# Sheet3.net
KiCad netlist of a schematic drawn in Altium Designer
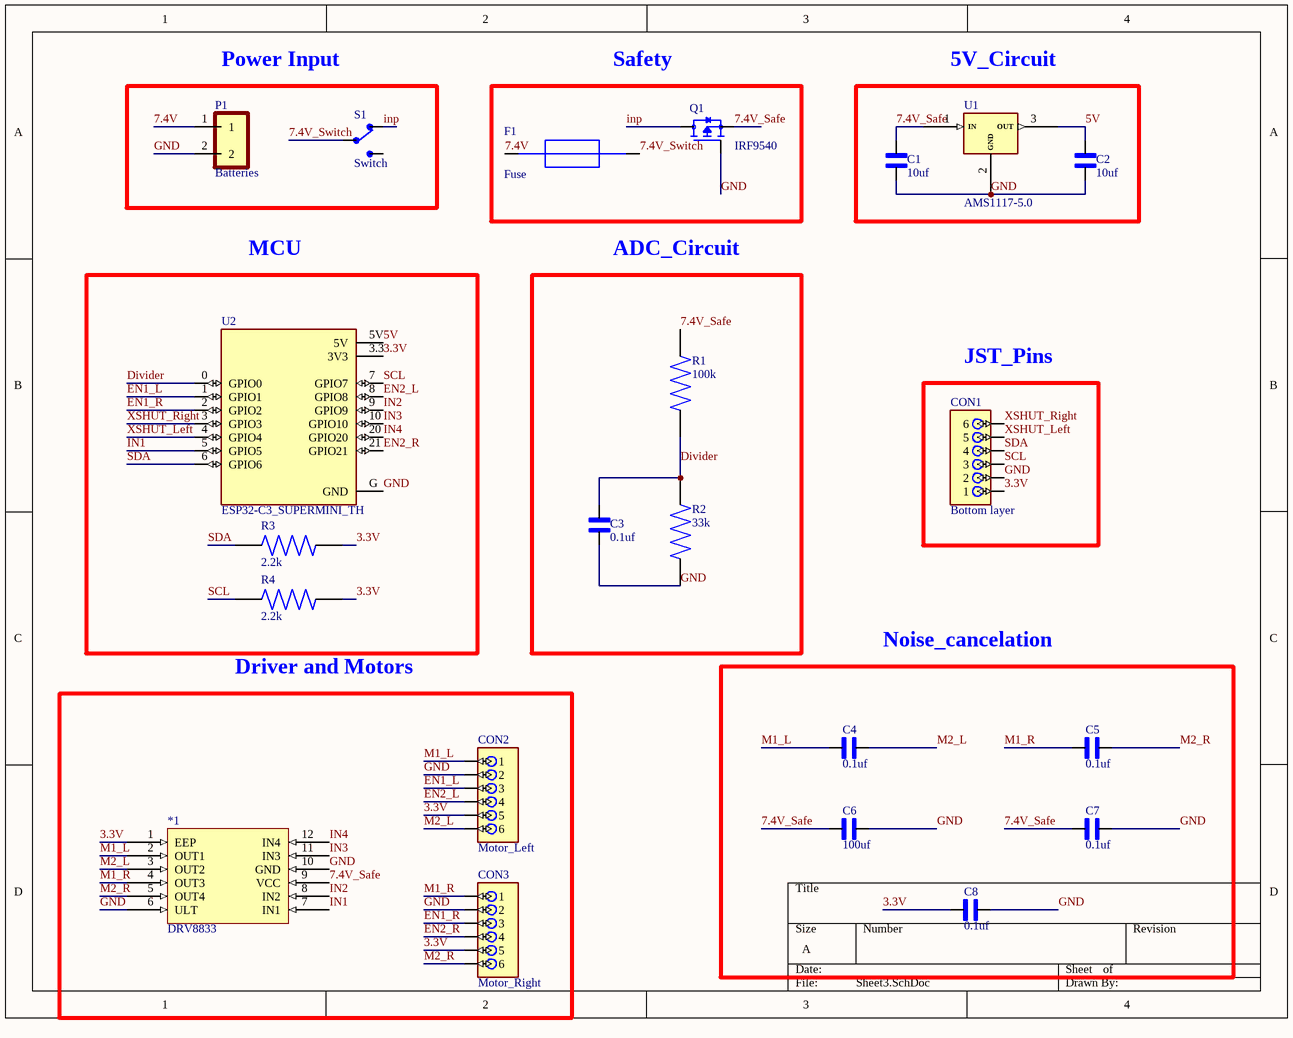
[diagram p0: Sheet3.SchDoc]

(export (version "E")
  (design (tool "Eeschema 10.0.6"))
  (components
    (comp (ref "*1") (value "DRV8833") (footprint "MOD-DRV8833") (libsource (lib "Schlib1") (part "DRV8833")))
    (comp (ref "C1")
      (value "10uf")
      (footprint "CAP_ECHU1H181GX5")
      (description "Capacitor Pps Film, 180pf, 50v, 2%, 0805capacitor Pps Film, 180pf, 50v, 2%, 0805")
      (fields (field (name "MF") "Panasonic") (field (name "DIGI-KEY_PART_NUMBER") "PCF1287TR-ND"))
      (libsource (lib "") (part "ECHU1H181GX5_1"))
    )
    (comp (ref "C2")
      (value "10uf")
      (footprint "CAP_ECHU1H181GX5")
      (description "Capacitor Pps Film, 180pf, 50v, 2%, 0805capacitor Pps Film, 180pf, 50v, 2%, 0805")
      (fields (field (name "MF") "Panasonic") (field (name "DIGI-KEY_PART_NUMBER") "PCF1287TR-ND"))
      (libsource (lib "") (part "ECHU1H181GX5_1"))
    )
    (comp (ref "C3")
      (value "0.1uf")
      (footprint "CAP_ECHU1H181GX5")
      (description "Capacitor Pps Film, 180pf, 50v, 2%, 0805capacitor Pps Film, 180pf, 50v, 2%, 0805")
      (fields (field (name "MF") "Panasonic") (field (name "DIGI-KEY_PART_NUMBER") "PCF1287TR-ND"))
      (libsource (lib "") (part "ECHU1H181GX5_1"))
    )
    (comp (ref "C4")
      (value "0.1uf")
      (footprint "CAP_ECHU1H181GX5")
      (description "Capacitor Pps Film, 180pf, 50v, 2%, 0805capacitor Pps Film, 180pf, 50v, 2%, 0805")
      (fields (field (name "MF") "Panasonic") (field (name "DIGI-KEY_PART_NUMBER") "PCF1287TR-ND"))
      (libsource (lib "Schlib1") (part "ECHU1H181GX5"))
    )
    (comp (ref "C5")
      (value "0.1uf")
      (footprint "CAP_ECHU1H181GX5")
      (description "Capacitor Pps Film, 180pf, 50v, 2%, 0805capacitor Pps Film, 180pf, 50v, 2%, 0805")
      (fields (field (name "MF") "Panasonic") (field (name "DIGI-KEY_PART_NUMBER") "PCF1287TR-ND"))
      (libsource (lib "Schlib1") (part "ECHU1H181GX5"))
    )
    (comp (ref "C6")
      (value "100uf")
      (footprint "CAPC3225X280N")
      (description "100 ÂµF Â±20% 6.3V Ceramic Capacitor X5R 1210 (3225 Metric)")
      (fields (field (name "MF") "Samsung") (field (name "MP") "CL32A107MQVNNWE"))
      (libsource (lib "Schlib1") (part "CL32A107MQVNNWE"))
    )
    (comp (ref "C7")
      (value "0.1uf")
      (footprint "CAPC3225X280N")
      (description "100 ÂµF Â±20% 6.3V Ceramic Capacitor X5R 1210 (3225 Metric)")
      (fields (field (name "MF") "Samsung") (field (name "MP") "CL32A107MQVNNWE"))
      (libsource (lib "Schlib1") (part "CL32A107MQVNNWE"))
    )
    (comp (ref "C8")
      (value "0.1uf")
      (footprint "CAPC3225X280N")
      (description "100 ÂµF Â±20% 6.3V Ceramic Capacitor X5R 1210 (3225 Metric)")
      (fields (field (name "MF") "Samsung") (field (name "MP") "CL32A107MQVNNWE"))
      (libsource (lib "Schlib1") (part "CL32A107MQVNNWE"))
    )
    (comp (ref "CON1")
      (value "Bottom layer")
      (footprint "6 pin JST")
      (description "Connector Header Surface Mount 6 position 0.059 (1.50mm)")
      (fields (field (name "MF") "JST") (field (name "MP") "B6B-ZR"))
      (libsource (lib "") (part "6 pin JST_1"))
    )
    (comp (ref "CON2")
      (value "Motor_Left")
      (footprint "6 pin JST")
      (description "Connector Header Surface Mount 6 position 0.059 (1.50mm)")
      (fields (field (name "MF") "JST") (field (name "MP") "B6B-ZR"))
      (libsource (lib "Schlib1") (part "6 pin JST"))
    )
    (comp (ref "CON3")
      (value "Motor_Right")
      (footprint "6 pin JST")
      (description "Connector Header Surface Mount 6 position 0.059 (1.50mm)")
      (fields (field (name "MF") "JST") (field (name "MP") "B6B-ZR"))
      (libsource (lib "Schlib1") (part "6 pin JST"))
    )
    (comp (ref "F1")
      (value "Fuse")
      (footprint "FUSC3216X75N")
      (description "Polymeric PTC Resettable Fuse 6V 350 mA Ih Surface Mount 1206 (3216 Metric), Concave")
      (fields (field (name "MF") "Littelfuse Inc.") (field (name "MP") "1206L035YR"))
      (libsource (lib "Schlib1") (part "1206L035YR"))
    )
    (comp (ref "P1")
      (value "Batteries")
      (footprint "Green Terminal")
      (fields (field (name "MF") "TE Connectivity") (field (name "MP") "282837-2"))
      (libsource (lib "Schlib1") (part "Green Terminal"))
    )
    (comp (ref "Q1")
      (value "IRF9540")
      (footprint "TO254P1052X465X1989-3")
      (description "P-Channel 100 V 19A (Tc) 3.7W (Ta), 150W (Tc) Surface Mount DÂ²PAK (TO-263)")
      (fields (field (name "MF") "Vishay"))
      (libsource (lib "Schlib1") (part "IRF9540"))
    )
    (comp (ref "R1")
      (value "100k")
      (footprint "SMD R")
      (fields (field (name "MP") "ERJU06F91R0V"))
      (libsource (lib "My_library") (part "SMD R 0805"))
    )
    (comp (ref "R2")
      (value "33k")
      (footprint "SMD R")
      (fields (field (name "MP") "ERJU06F91R0V"))
      (libsource (lib "My_library") (part "SMD R 0805"))
    )
    (comp (ref "R3")
      (value "2.2k")
      (footprint "SMD R")
      (fields (field (name "MP") "ERJU06F91R0V"))
      (libsource (lib "My_library") (part "SMD R 0805"))
    )
    (comp (ref "R4")
      (value "2.2k")
      (footprint "SMD R")
      (fields (field (name "MP") "ERJU06F91R0V"))
      (libsource (lib "My_library") (part "SMD R 0805"))
    )
    (comp (ref "S1")
      (value "Switch")
      (footprint "SW_1101M2S3CQE2")
      (description "Switch,Slide,Sealed,SPDT,ON-NONE-ON,PC Mnt,.200 Blk Act,6A,120VAC,PC Thru-Hole ¦ C&K 1101M2S3CQE2")
      (fields (field (name "MF") "C&K") (field (name "MP") "1101M2S3CQE2"))
      (libsource (lib "My_library") (part "1101M2S3CQE2"))
    )
    (comp (ref "U1")
      (value "AMS1117-5.0")
      (footprint "5V Regulator")
      (libsource (lib "Schlib1") (part "5V Regulator"))
    )
    (comp (ref "U2")
      (value "ESP32-C3_SUPERMINI_TH")
      (footprint "MODULE_ESP32-C3_SUPERMINI_TH")
      (description "Super tiny ESP32-C3 board")
      (fields (field (name "MF") "Espressif Systems") (field (name "MP") "ESP32-C3 SuperMini_TH"))
      (libsource (lib "Schlib1") (part "ESP32-C3_SUPERMINI_TH"))
    )
  )
  (nets
    (net (code "1") (name "/3.3V") (class "Default")
      (node (ref "*1") (pin "1") (pinfunction "EEP_1") (pintype "input"))
      (node (ref "C8") (pin "1") (pinfunction "1_1") (pintype "passive"))
      (node (ref "CON1") (pin "1") (pinfunction "1_1") (pintype "bidirectional"))
      (node (ref "CON2") (pin "5") (pinfunction "5_5") (pintype "bidirectional"))
      (node (ref "CON3") (pin "5") (pinfunction "5_5") (pintype "bidirectional"))
      (node (ref "R3") (pin "2") (pintype "passive"))
      (node (ref "R4") (pin "2") (pintype "passive"))
      (node (ref "U2") (pin "3.3") (pinfunction "3V3_3.3") (pintype "power_in"))
    )
    (net (code "2") (name "/5V") (class "Default")
      (node (ref "C2") (pin "2") (pinfunction "2_2") (pintype "passive"))
      (node (ref "U1") (pin "3") (pinfunction "OUT_3") (pintype "output"))
      (node (ref "U2") (pin "5V") (pinfunction "5V_5V") (pintype "power_in"))
    )
    (net (code "3") (name "/7.4V") (class "Default")
      (node (ref "F1") (pin "1") (pinfunction "1_1") (pintype "passive"))
      (node (ref "P1") (pin "1") (pinfunction "1_1") (pintype "passive"))
    )
    (net (code "4") (name "/7.4V_Safe") (class "Default")
      (node (ref "*1") (pin "9") (pinfunction "VCC_9") (pintype "input"))
      (node (ref "C1") (pin "2") (pinfunction "2_2") (pintype "passive"))
      (node (ref "C6") (pin "1") (pinfunction "1_1") (pintype "passive"))
      (node (ref "C7") (pin "1") (pinfunction "1_1") (pintype "passive"))
      (node (ref "Q1") (pin "3") (pinfunction "S_3") (pintype "passive"))
      (node (ref "R1") (pin "1") (pintype "passive"))
      (node (ref "U1") (pin "1") (pinfunction "IN_1") (pintype "input"))
    )
    (net (code "5") (name "/7.4V_Switch") (class "Default")
      (node (ref "F1") (pin "2") (pinfunction "2_2") (pintype "passive"))
      (node (ref "S1") (pin "2") (pinfunction "2_2") (pintype "passive"))
    )
    (net (code "6") (name "/Divider") (class "Default")
      (node (ref "C3") (pin "2") (pinfunction "2_2") (pintype "passive"))
      (node (ref "R1") (pin "2") (pintype "passive"))
      (node (ref "R2") (pin "1") (pintype "passive"))
      (node (ref "U2") (pin "0") (pinfunction "GPIO0_0") (pintype "bidirectional"))
    )
    (net (code "7") (name "/EN1_L") (class "Default")
      (node (ref "CON2") (pin "3") (pinfunction "3_3") (pintype "bidirectional"))
      (node (ref "U2") (pin "1") (pinfunction "GPIO1_1") (pintype "bidirectional"))
    )
    (net (code "8") (name "/EN1_R") (class "Default")
      (node (ref "CON3") (pin "3") (pinfunction "3_3") (pintype "bidirectional"))
      (node (ref "U2") (pin "2") (pinfunction "GPIO2_2") (pintype "bidirectional"))
    )
    (net (code "9") (name "/EN2_L") (class "Default")
      (node (ref "CON2") (pin "4") (pinfunction "4_4") (pintype "bidirectional"))
      (node (ref "U2") (pin "8") (pinfunction "GPIO8_8") (pintype "bidirectional"))
    )
    (net (code "10") (name "/EN2_R") (class "Default")
      (node (ref "CON3") (pin "4") (pinfunction "4_4") (pintype "bidirectional"))
      (node (ref "U2") (pin "21") (pinfunction "GPIO21_21") (pintype "bidirectional"))
    )
    (net (code "11") (name "/GND") (class "Default")
      (node (ref "*1") (pin "10") (pinfunction "GND_10") (pintype "input"))
      (node (ref "*1") (pin "6") (pinfunction "ULT_6") (pintype "input"))
      (node (ref "C1") (pin "1") (pinfunction "1_1") (pintype "passive"))
      (node (ref "C2") (pin "1") (pinfunction "1_1") (pintype "passive"))
      (node (ref "C3") (pin "1") (pinfunction "1_1") (pintype "passive"))
      (node (ref "C6") (pin "2") (pinfunction "2_2") (pintype "passive"))
      (node (ref "C7") (pin "2") (pinfunction "2_2") (pintype "passive"))
      (node (ref "C8") (pin "2") (pinfunction "2_2") (pintype "passive"))
      (node (ref "CON1") (pin "2") (pinfunction "2_2") (pintype "bidirectional"))
      (node (ref "CON2") (pin "2") (pinfunction "2_2") (pintype "bidirectional"))
      (node (ref "CON3") (pin "2") (pinfunction "2_2") (pintype "bidirectional"))
      (node (ref "P1") (pin "2") (pinfunction "2_2") (pintype "passive"))
      (node (ref "Q1") (pin "1") (pinfunction "G_1") (pintype "passive"))
      (node (ref "R2") (pin "2") (pintype "passive"))
      (node (ref "U1") (pin "2") (pinfunction "GND_2") (pintype "power_in"))
      (node (ref "U2") (pin "G") (pinfunction "GND_G") (pintype "power_in"))
    )
    (net (code "12") (name "/IN1") (class "Default")
      (node (ref "*1") (pin "7") (pinfunction "IN1_7") (pintype "input"))
      (node (ref "U2") (pin "5") (pinfunction "GPIO5_5") (pintype "bidirectional"))
    )
    (net (code "13") (name "/IN2") (class "Default")
      (node (ref "*1") (pin "8") (pinfunction "IN2_8") (pintype "input"))
      (node (ref "U2") (pin "9") (pinfunction "GPIO9_9") (pintype "bidirectional"))
    )
    (net (code "14") (name "/IN3") (class "Default")
      (node (ref "*1") (pin "11") (pinfunction "IN3_11") (pintype "input"))
      (node (ref "U2") (pin "10") (pinfunction "GPIO10_10") (pintype "bidirectional"))
    )
    (net (code "15") (name "/IN4") (class "Default")
      (node (ref "*1") (pin "12") (pinfunction "IN4_12") (pintype "input"))
      (node (ref "U2") (pin "20") (pinfunction "GPIO20_20") (pintype "bidirectional"))
    )
    (net (code "16") (name "/M1_L") (class "Default")
      (node (ref "*1") (pin "2") (pinfunction "OUT1_2") (pintype "input"))
      (node (ref "C4") (pin "2") (pinfunction "2_2") (pintype "passive"))
      (node (ref "CON2") (pin "1") (pinfunction "1_1") (pintype "bidirectional"))
    )
    (net (code "17") (name "/M1_R") (class "Default")
      (node (ref "*1") (pin "4") (pinfunction "OUT3_4") (pintype "input"))
      (node (ref "C5") (pin "2") (pinfunction "2_2") (pintype "passive"))
      (node (ref "CON3") (pin "1") (pinfunction "1_1") (pintype "bidirectional"))
    )
    (net (code "18") (name "/M2_L") (class "Default")
      (node (ref "*1") (pin "3") (pinfunction "OUT2_3") (pintype "input"))
      (node (ref "C4") (pin "1") (pinfunction "1_1") (pintype "passive"))
      (node (ref "CON2") (pin "6") (pinfunction "6_6") (pintype "bidirectional"))
    )
    (net (code "19") (name "/M2_R") (class "Default")
      (node (ref "*1") (pin "5") (pinfunction "OUT4_5") (pintype "input"))
      (node (ref "C5") (pin "1") (pinfunction "1_1") (pintype "passive"))
      (node (ref "CON3") (pin "6") (pinfunction "6_6") (pintype "bidirectional"))
    )
    (net (code "20") (name "/SCL") (class "Default")
      (node (ref "CON1") (pin "3") (pinfunction "3_3") (pintype "bidirectional"))
      (node (ref "R4") (pin "1") (pintype "passive"))
      (node (ref "U2") (pin "7") (pinfunction "GPIO7_7") (pintype "bidirectional"))
    )
    (net (code "21") (name "/SDA") (class "Default")
      (node (ref "CON1") (pin "4") (pinfunction "4_4") (pintype "bidirectional"))
      (node (ref "R3") (pin "1") (pintype "passive"))
      (node (ref "U2") (pin "6") (pinfunction "GPIO6_6") (pintype "bidirectional"))
    )
    (net (code "22") (name "/XSHUT_Left") (class "Default")
      (node (ref "CON1") (pin "5") (pinfunction "5_5") (pintype "bidirectional"))
      (node (ref "U2") (pin "4") (pinfunction "GPIO4_4") (pintype "bidirectional"))
    )
    (net (code "23") (name "/XSHUT_Right") (class "Default")
      (node (ref "CON1") (pin "6") (pinfunction "6_6") (pintype "bidirectional"))
      (node (ref "U2") (pin "3") (pinfunction "GPIO3_3") (pintype "bidirectional"))
    )
    (net (code "24") (name "/inp") (class "Default")
      (node (ref "Q1") (pin "2") (pinfunction "D_2") (pintype "passive"))
      (node (ref "S1") (pin "1") (pinfunction "1_1") (pintype "passive"))
    )
    (net (code "25") (name "unconnected-(S1-Pad3)") (class "Default")
      (node (ref "S1") (pin "3") (pinfunction "3_3") (pintype "passive"))
    )
  )
)
